# OCB.net
KiCad netlist of a schematic drawn in Altium Designer
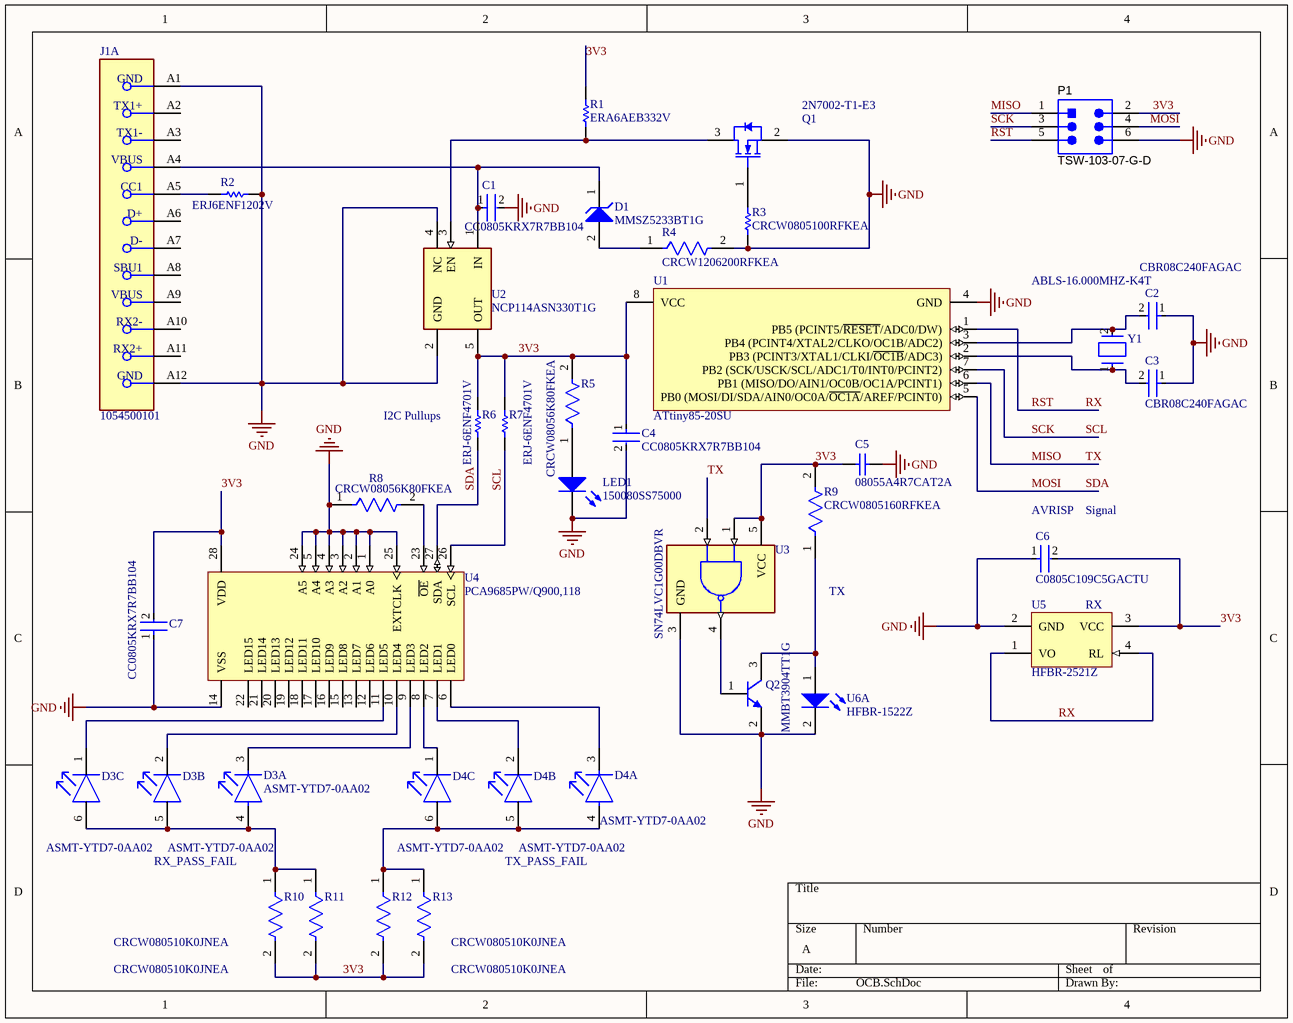
[diagram p0: OCB.SchDoc]

(export (version "E")
  (design (tool "Eeschema 10.0.6"))
  (components
    (comp (ref "C1")
      (value "CC0805KRX7R7BB104")
      (footprint "FP-CC0805-0_85-MFG")
      (description "CAP CER 0.1UF 16V X7R 0805")
      (fields
        (field (name "MANUFACTURER") "Yageo")
        (field (name "OCTOPART") "https://octopart.com/cc0805krx7r7bb104-yageo-39467769")
      )
      (libsource (lib "Altium Content Vault") (part "11868f565c42a9108669ba33697ecf6"))
    )
    (comp (ref "C2")
      (value "CBR08C240FAGAC")
      (footprint "FP-CBR08C-MFG")
      (description "CBR0805 24 pF C0G 30ppm/°C 1.00% 250 V")
      (fields (field (name "TOLERANCE") "0.01"))
      (libsource (lib "Altium Content Vault") (part "11868f565c42a9108669ba33697ecf6"))
    )
    (comp (ref "C3")
      (value "CBR08C240FAGAC")
      (footprint "FP-CBR08C-MFG")
      (description "CBR0805 24 pF C0G 30ppm/°C 1.00% 250 V")
      (fields (field (name "TOLERANCE") "0.01"))
      (libsource (lib "Altium Content Vault") (part "11868f565c42a9108669ba33697ecf6"))
    )
    (comp (ref "C4")
      (value "CC0805KRX7R7BB104")
      (footprint "FP-CC0805-0_85-MFG")
      (description "CAP CER 0.1UF 16V X7R 0805")
      (fields
        (field (name "MANUFACTURER") "Yageo")
        (field (name "OCTOPART") "https://octopart.com/cc0805krx7r7bb104-yageo-39467769")
      )
      (libsource (lib "Altium Content Vault") (part "11868f565c42a9108669ba33697ecf6"))
    )
    (comp (ref "C5")
      (value "08055A4R7CAT2A")
      (footprint "CAPC2013X71X50ML20T25")
      (fields (field (name "MANUFACTURER") "AVX Interconnect / Elco"))
      (libsource (lib "Altium Content Vault") (part "CAP"))
    )
    (comp (ref "C6")
      (value "C0805C109C5GACTU")
      (footprint "FP-C0805C-DN-MFG")
      (description "CAP CER 1PF 50V C0G/NP0 0805")
      (fields (field (name "MANUFACTURER") "KEMET") (field (name "TOLERANCE") "0.25 pF"))
      (libsource (lib "Altium Content Vault") (part "b4654b650e69147ec39a6b967a45e02"))
    )
    (comp (ref "C7")
      (value "CC0805KRX7R7BB104")
      (footprint "FP-CC0805-0_85-MFG")
      (description "CAP CER 0.1UF 16V X7R 0805")
      (fields
        (field (name "MANUFACTURER") "Yageo")
        (field (name "OCTOPART") "https://octopart.com/cc0805krx7r7bb104-yageo-39467769")
      )
      (libsource (lib "Altium Content Vault") (part "11868f565c42a9108669ba33697ecf6"))
    )
    (comp (ref "D1")
      (value "MMSZ5233BT1G")
      (footprint "ONSC-SOD-123-2-425-04_V")
      (description "Zener Voltage Regulator, 500 mW, 2-Pin SOD-123, Pb-Free, Tape and Reel")
      (fields (field (name "MANUFACTURER") "On Semiconductor"))
      (libsource (lib "Altium Content Vault") (part "ONSC-K1A2-2"))
    )
    (comp (ref "D3")
      (value "ASMT-YTD7-0AA02")
      (footprint "FP-PLCC-6-MFG")
      (description "LED RGB DIFFUSED 6PLCC SMD")
      (fields
        (field (name "MANUFACTURER") "Broadcom")
        (field (name "OCTOPART") "https://octopart.com/asmt-ytd7-0aa02-broadcom-71127359")
      )
      (libsource (lib "Altium Content Vault") (part "a8d7b0c4ab3168287692aa145c184e1"))
    )
    (comp (ref "D4")
      (value "ASMT-YTD7-0AA02")
      (footprint "FP-PLCC-6-MFG")
      (description "LED RGB DIFFUSED 6PLCC SMD")
      (fields
        (field (name "MANUFACTURER") "Broadcom")
        (field (name "OCTOPART") "https://octopart.com/asmt-ytd7-0aa02-broadcom-71127359")
      )
      (libsource (lib "Altium Content Vault") (part "a8d7b0c4ab3168287692aa145c184e1"))
    )
    (comp (ref "J1")
      (value "1054500101")
      (footprint "FP-1054500101-MFG")
      (description "CONN RCP USB3.1 TYPEC 24P SMD RA")
      (fields
        (field (name "MANUFACTURER") "Molex")
        (field (name "OCTOPART") "https://octopart.com/105450-0101-molex-68082325")
      )
      (libsource (lib "Altium Content Vault") (part "9808b19ecaf079fb99eed69f0495cd0"))
    )
    (comp (ref "LED1")
      (value "150080SS75000")
      (footprint "0805_A")
      (description "SMD mono-color Chip LED, WL-SMCW, Super Red")
      (fields (field (name "MANUFACTURER") "Wuerth Elektronik"))
      (libsource (lib "Altium Content Vault") (part "WE-LED_K1A2-2"))
    )
    (comp (ref "P1")
      (value "TSW-103-07-G-D")
      (footprint "SMTC-TSW-103-07-G-D_V")
      (fields (field (name "MANUFACTURER") "Samtec-Inc."))
      (libsource (lib "Altium Content Vault") (part "CN-2P-M-R6"))
    )
    (comp (ref "Q1")
      (value "2N7002-T1-E3")
      (footprint "VISH-TO-236-3_A_L")
      (description "N-Channel MOSFET, 115 mA, 60 V, -55 to 150 degC, 3-Pin SOT23, RoHS, Tape and Reel")
      (fields (field (name "MANUFACTURER") "Vishay"))
      (libsource (lib "Altium Content Vault") (part "NEMOS-GSD-3"))
    )
    (comp (ref "Q2")
      (value "MMBT3904TT1G")
      (footprint "ONSC-SC-75-3-463-01_V")
      (description "General Purpose Transistor, NPN Silicon, 3-Pin SC-75, Pb-Free, Tape and Reel")
      (fields (field (name "MANUFACTURER") "On Semiconductor"))
      (libsource (lib "Altium Content Vault") (part "ONSC-NPN-B1E2C3-3"))
    )
    (comp (ref "R1")
      (value "ERA6AEB332V")
      (footprint "RESC2013X60X40NL20T25")
      (fields (field (name "MANUFACTURER") "Panasonic"))
      (libsource (lib "Altium Content Vault") (part "RES"))
    )
    (comp (ref "R2")
      (value "ERJ6ENF1202V")
      (footprint "RESC2013X70X40ML20T20")
      (fields (field (name "MANUFACTURER") "Panasonic"))
      (libsource (lib "Altium Content Vault") (part "RES"))
    )
    (comp (ref "R3")
      (value "CRCW0805100RFKEA")
      (footprint "RESC2013X50X30LL20T20")
      (fields (field (name "MANUFACTURER") "Vishay Dale"))
      (libsource (lib "Altium Content Vault") (part "RES"))
    )
    (comp (ref "R4")
      (value "CRCW1206200RFKEA")
      (footprint "FP-CRCW1206-e3-IPC_C")
      (description "RES Thick Film, 200Ω, 1%, 0.25W, 100ppm/°C, 1206")
      (fields (field (name "TOLERANCE") "1%"))
      (libsource (lib "Altium Content Vault") (part "1029c3af85768c4190bb7ad29bc67b5"))
    )
    (comp (ref "R5")
      (value "CRCW08056K80FKEA")
      (footprint "FP-CRCW0805-e3-IPC_A")
      (description "RES Thick Film, 6.8kΩ, 1%, 0.125W, 100ppm/°C, 0805")
      (fields (field (name "TOLERANCE") "1%"))
      (libsource (lib "Altium Content Vault") (part "1029c3af85768c4190bb7ad29bc67b5"))
    )
    (comp (ref "R6")
      (value "ERJ-6ENF4701V")
      (footprint "RESC2013X70X40NL20T20")
      (description "Chip Resistor, 4.7 KOhm, +/- 1%, 0.125 W, -55 to 155 degC, 0805 (2012 Metric), RoHS, Tape and Reel")
      (fields (field (name "MANUFACTURER") "Panasonic"))
      (libsource (lib "Altium Content Vault") (part "RES-2"))
    )
    (comp (ref "R7")
      (value "ERJ-6ENF4701V")
      (footprint "RESC2013X70X40NL20T20")
      (description "Chip Resistor, 4.7 KOhm, +/- 1%, 0.125 W, -55 to 155 degC, 0805 (2012 Metric), RoHS, Tape and Reel")
      (fields (field (name "MANUFACTURER") "Panasonic"))
      (libsource (lib "Altium Content Vault") (part "RES-2"))
    )
    (comp (ref "R8")
      (value "CRCW08056K80FKEA")
      (footprint "FP-CRCW0805-e3-IPC_A")
      (description "RES Thick Film, 6.8kΩ, 1%, 0.125W, 100ppm/°C, 0805")
      (fields (field (name "TOLERANCE") "1%"))
      (libsource (lib "Altium Content Vault") (part "1029c3af85768c4190bb7ad29bc67b5"))
    )
    (comp (ref "R9")
      (value "CRCW0805160RFKEA")
      (footprint "FP-CRCW0805-e3-IPC_C")
      (description "RES Thick Film, 160Ω, 1%, 0.125W, 100ppm/°C, 0805")
      (fields (field (name "TOLERANCE") "1%"))
      (libsource (lib "Altium Content Vault") (part "1029c3af85768c4190bb7ad29bc67b5"))
    )
    (comp (ref "R10")
      (value "CRCW080510K0JNEA")
      (footprint "FP-CRCW0805-e3-IPC_C")
      (description "RES Thick Film, 10kΩ, 5%, 0.125W, 200ppm/°C, 0805")
      (fields (field (name "TOLERANCE") "5%"))
      (libsource (lib "Altium Content Vault") (part "1029c3af85768c4190bb7ad29bc67b5"))
    )
    (comp (ref "R11")
      (value "CRCW080510K0JNEA")
      (footprint "FP-CRCW0805-e3-IPC_C")
      (description "RES Thick Film, 10kΩ, 5%, 0.125W, 200ppm/°C, 0805")
      (fields (field (name "TOLERANCE") "5%"))
      (libsource (lib "Altium Content Vault") (part "1029c3af85768c4190bb7ad29bc67b5"))
    )
    (comp (ref "R12")
      (value "CRCW080510K0JNEA")
      (footprint "FP-CRCW0805-e3-IPC_C")
      (description "RES Thick Film, 10kΩ, 5%, 0.125W, 200ppm/°C, 0805")
      (fields (field (name "TOLERANCE") "5%"))
      (libsource (lib "Altium Content Vault") (part "1029c3af85768c4190bb7ad29bc67b5"))
    )
    (comp (ref "R13")
      (value "CRCW080510K0JNEA")
      (footprint "FP-CRCW0805-e3-IPC_C")
      (description "RES Thick Film, 10kΩ, 5%, 0.125W, 200ppm/°C, 0805")
      (fields (field (name "TOLERANCE") "5%"))
      (libsource (lib "Altium Content Vault") (part "1029c3af85768c4190bb7ad29bc67b5"))
    )
    (comp (ref "U1")
      (value "ATtiny85-20SU")
      (footprint "8S2_M")
      (libsource (lib "Altium Content Vault") (part "MC-8B-ATT25-IL8"))
    )
    (comp (ref "U2")
      (value "NCP114ASN330T1G")
      (footprint "FP-483-MFG")
      (description "IC REG LINEAR 3.3V 300MA 5TSOP")
      (fields
        (field (name "MANUFACTURER") "ON Semiconductor")
        (field (name "OCTOPART") "https://octopart.com/ncp114asn330t1g-on+semiconductor-74628742")
      )
      (libsource (lib "Altium Content Vault") (part "57814aa37072aacea77ef0fe9350350"))
    )
    (comp (ref "U3")
      (value "SN74LVC1G00DBVR")
      (footprint "FP-DBV0005A-MFG")
      (description "IC GATE NAND 1CH 2-INP SOT23-5")
      (fields
        (field (name "MANUFACTURER") "Texas Instruments")
        (field (name "OCTOPART") "https://octopart.com/sn74lvc1g00dbvr-texas+instruments-465560")
      )
      (libsource (lib "Altium Content Vault") (part "d7ecd29f903bbf85ac132faf7c71588"))
    )
    (comp (ref "U4")
      (value "PCA9685PW/Q900,118")
      (footprint "SOT361-1_V")
      (fields (field (name "PARTNUMBER") "PCA9685"))
      (libsource (lib "Altium Content Vault") (part "NXP-PCA9685-SOT361-1"))
    )
    (comp (ref "U5")
      (value "HFBR-2521Z")
      (footprint "BCM-HFBR-2521Z-4")
      (description "The Versatile Fiber Optic Connection, 5 MBd, -40 to 85 degC, 4-Pin, RoHS, Rail/Tube")
      (fields (field (name "MANUFACTURER") "Broadcom"))
      (libsource (lib "Altium Content Vault") (part "BCM-HFBR-2521Z-4"))
    )
    (comp (ref "U6")
      (value "HFBR-1522Z")
      (footprint "AVAG-HFBR-15X2Z_V")
      (description "The Versatile Fiber Optic Connection, 5 V, -40 to 85 degC, 6-Pin THD, RoHS, Tube")
      (fields (field (name "MANUFACTURER") "Avago"))
      (libsource (lib "Altium Content Vault") (part "AVAG-HFBR-15X2Z-6"))
    )
    (comp (ref "Y1")
      (value "ABLS-16.000MHZ-K4T")
      (footprint "FP-ABLS-MFG")
      (description "CRYSTAL 16.0000MHZ 18PF SMD")
      (fields
        (field (name "TOLERANCE") "30ppm")
        (field (name "OCTOPART") "https://octopart.com/abls-16.000mhz-k4t-abracon-18618626")
      )
      (libsource (lib "Altium Content Vault") (part "c23a69dc6c9e2f18f2079038eb95dd1"))
    )
  )
  (nets
    (net (code "1") (name "/3V3") (class "Default")
      (node (ref "C4") (pin "1") (pinfunction "1_1") (pintype "passive"))
      (node (ref "C5") (pin "2") (pinfunction "2_2") (pintype "passive"))
      (node (ref "C6") (pin "2") (pinfunction "2_2") (pintype "passive"))
      (node (ref "C7") (pin "2") (pinfunction "2_2") (pintype "passive"))
      (node (ref "P1") (pin "2") (pinfunction "2_2") (pintype "passive"))
      (node (ref "R1") (pin "2") (pinfunction "2_2") (pintype "passive"))
      (node (ref "R10") (pin "2") (pinfunction "2_2") (pintype "passive"))
      (node (ref "R11") (pin "2") (pinfunction "2_2") (pintype "passive"))
      (node (ref "R12") (pin "2") (pinfunction "2_2") (pintype "passive"))
      (node (ref "R13") (pin "2") (pinfunction "2_2") (pintype "passive"))
      (node (ref "R5") (pin "2") (pinfunction "2_2") (pintype "passive"))
      (node (ref "R6") (pin "2") (pinfunction "2_2") (pintype "passive"))
      (node (ref "R7") (pin "2") (pinfunction "2_2") (pintype "passive"))
      (node (ref "R9") (pin "2") (pinfunction "2_2") (pintype "passive"))
      (node (ref "U1") (pin "8") (pinfunction "VCC_8") (pintype "power_in"))
      (node (ref "U2") (pin "5") (pinfunction "OUT_5") (pintype "power_in"))
      (node (ref "U3") (pin "1") (pinfunction "A_1") (pintype "input"))
      (node (ref "U3") (pin "5") (pinfunction "VCC_5") (pintype "power_in"))
      (node (ref "U4") (pin "28") (pinfunction "VDD_28") (pintype "power_in"))
      (node (ref "U5") (pin "3") (pinfunction "VCC_3") (pintype "power_in"))
    )
    (net (code "2") (name "/MISO") (class "Default")
      (node (ref "P1") (pin "1") (pinfunction "1_1") (pintype "passive"))
      (node (ref "U1") (pin "6") (pinfunction "PB1_(MISO/DO/AIN1/OC0B/OC1A/PCINT1)_6") (pintype "bidirectional"))
      (node (ref "U3") (pin "2") (pinfunction "B_2") (pintype "input"))
    )
    (net (code "3") (name "/MOSI") (class "Default")
      (node (ref "P1") (pin "4") (pinfunction "4_4") (pintype "passive"))
      (node (ref "R6") (pin "1") (pinfunction "1_1") (pintype "passive"))
      (node (ref "U1") (pin "5") (pinfunction "PB0_(MOSI/DI/SDA/AIN0/OC0A/~{OC1A}/AREF/PCINT0)_5") (pintype "bidirectional"))
      (node (ref "U4") (pin "27") (pinfunction "SDA_27") (pintype "bidirectional"))
    )
    (net (code "4") (name "/RST") (class "Default")
      (node (ref "P1") (pin "5") (pinfunction "5_5") (pintype "passive"))
      (node (ref "U1") (pin "1") (pinfunction "PB5_(PCINT5/~{RESET}/ADC0/DW)_1") (pintype "bidirectional"))
      (node (ref "U5") (pin "1") (pinfunction "VO_1") (pintype "power_in"))
      (node (ref "U5") (pin "4") (pinfunction "RL_4") (pintype "input"))
    )
    (net (code "5") (name "/SCK") (class "Default")
      (node (ref "P1") (pin "3") (pinfunction "3_3") (pintype "passive"))
      (node (ref "R7") (pin "1") (pinfunction "1_1") (pintype "passive"))
      (node (ref "U1") (pin "7") (pinfunction "PB2_(SCK/USCK/SCL/ADC1/T0/INT0/PCINT2)_7") (pintype "bidirectional"))
      (node (ref "U4") (pin "26") (pinfunction "SCL_26") (pintype "input"))
    )
    (net (code "6") (name "GND") (class "Default")
      (node (ref "C1") (pin "2") (pinfunction "2_2") (pintype "passive"))
      (node (ref "C2") (pin "1") (pinfunction "1_1") (pintype "passive"))
      (node (ref "C3") (pin "1") (pinfunction "1_1") (pintype "passive"))
      (node (ref "C4") (pin "2") (pinfunction "2_2") (pintype "passive"))
      (node (ref "C5") (pin "1") (pinfunction "1_1") (pintype "passive"))
      (node (ref "C6") (pin "1") (pinfunction "1_1") (pintype "passive"))
      (node (ref "C7") (pin "1") (pinfunction "1_1") (pintype "passive"))
      (node (ref "J1") (pin "A1") (pinfunction "GND_A1") (pintype "passive"))
      (node (ref "J1") (pin "A12") (pinfunction "GND_A12") (pintype "passive"))
      (node (ref "LED1") (pin "1") (pinfunction "K_1") (pintype "passive"))
      (node (ref "P1") (pin "6") (pinfunction "6_6") (pintype "passive"))
      (node (ref "Q1") (pin "2") (pinfunction "S_2") (pintype "passive"))
      (node (ref "Q2") (pin "2") (pinfunction "E_2") (pintype "passive"))
      (node (ref "R2") (pin "2") (pinfunction "2_2") (pintype "passive"))
      (node (ref "R3") (pin "1") (pinfunction "1_1") (pintype "passive"))
      (node (ref "R4") (pin "2") (pinfunction "2_2") (pintype "passive"))
      (node (ref "R8") (pin "1") (pinfunction "1_1") (pintype "passive"))
      (node (ref "U1") (pin "4") (pinfunction "GND_4") (pintype "power_in"))
      (node (ref "U2") (pin "2") (pinfunction "GND_2") (pintype "power_in"))
      (node (ref "U2") (pin "4") (pinfunction "NC_4") (pintype "passive"))
      (node (ref "U3") (pin "3") (pinfunction "GND_3") (pintype "power_in"))
      (node (ref "U4") (pin "1") (pinfunction "A0_1") (pintype "input"))
      (node (ref "U4") (pin "14") (pinfunction "VSS_14") (pintype "power_in"))
      (node (ref "U4") (pin "2") (pinfunction "A1_2") (pintype "input"))
      (node (ref "U4") (pin "24") (pinfunction "A5_24") (pintype "input"))
      (node (ref "U4") (pin "25") (pinfunction "EXTCLK_25") (pintype "input"))
      (node (ref "U4") (pin "3") (pinfunction "A2_3") (pintype "input"))
      (node (ref "U4") (pin "4") (pinfunction "A3_4") (pintype "input"))
      (node (ref "U4") (pin "5") (pinfunction "A4_5") (pintype "input"))
      (node (ref "U5") (pin "2") (pinfunction "GND_2") (pintype "power_in"))
      (node (ref "U6") (pin "2") (pinfunction "CATHODE_2") (pintype "passive"))
    )
    (net (code "7") (name "Net-(D1-A)") (class "Default")
      (node (ref "D1") (pin "2") (pinfunction "A_2") (pintype "passive"))
      (node (ref "R4") (pin "1") (pinfunction "1_1") (pintype "passive"))
    )
    (net (code "8") (name "Net-(D1-K)") (class "Default")
      (node (ref "C1") (pin "1") (pinfunction "1_1") (pintype "passive"))
      (node (ref "D1") (pin "1") (pinfunction "K_1") (pintype "passive"))
      (node (ref "J1") (pin "A4") (pinfunction "VBUS_A4") (pintype "passive"))
      (node (ref "U2") (pin "1") (pinfunction "IN_1") (pintype "power_in"))
    )
    (net (code "9") (name "Net-(D3A-Anode(Red))") (class "Default")
      (node (ref "D3") (pin "4") (pinfunction "Anode(Red)_4") (pintype "passive"))
      (node (ref "D3") (pin "5") (pinfunction "Anode(Green)_5") (pintype "passive"))
      (node (ref "D3") (pin "6") (pinfunction "Anode(Blue)_6") (pintype "passive"))
      (node (ref "R10") (pin "1") (pinfunction "1_1") (pintype "passive"))
      (node (ref "R11") (pin "1") (pinfunction "1_1") (pintype "passive"))
    )
    (net (code "10") (name "Net-(D3A-Cathode(Red))") (class "Default")
      (node (ref "D3") (pin "3") (pinfunction "Cathode(Red)_3") (pintype "passive"))
      (node (ref "U4") (pin "9") (pinfunction "LED3_9") (pintype "tri_state"))
    )
    (net (code "11") (name "Net-(D3B-Cathode(Green))") (class "Default")
      (node (ref "D3") (pin "2") (pinfunction "Cathode(Green)_2") (pintype "passive"))
      (node (ref "U4") (pin "10") (pinfunction "LED4_10") (pintype "tri_state"))
    )
    (net (code "12") (name "Net-(D3C-Cathode(Blue))") (class "Default")
      (node (ref "D3") (pin "1") (pinfunction "Cathode(Blue)_1") (pintype "passive"))
      (node (ref "U4") (pin "11") (pinfunction "LED5_11") (pintype "tri_state"))
    )
    (net (code "13") (name "Net-(D4A-Anode(Red))") (class "Default")
      (node (ref "D4") (pin "4") (pinfunction "Anode(Red)_4") (pintype "passive"))
      (node (ref "D4") (pin "5") (pinfunction "Anode(Green)_5") (pintype "passive"))
      (node (ref "D4") (pin "6") (pinfunction "Anode(Blue)_6") (pintype "passive"))
      (node (ref "R12") (pin "1") (pinfunction "1_1") (pintype "passive"))
      (node (ref "R13") (pin "1") (pinfunction "1_1") (pintype "passive"))
    )
    (net (code "14") (name "Net-(D4A-Cathode(Red))") (class "Default")
      (node (ref "D4") (pin "3") (pinfunction "Cathode(Red)_3") (pintype "passive"))
      (node (ref "U4") (pin "6") (pinfunction "LED0_6") (pintype "tri_state"))
    )
    (net (code "15") (name "Net-(D4B-Cathode(Green))") (class "Default")
      (node (ref "D4") (pin "2") (pinfunction "Cathode(Green)_2") (pintype "passive"))
      (node (ref "U4") (pin "7") (pinfunction "LED1_7") (pintype "tri_state"))
    )
    (net (code "16") (name "Net-(D4C-Cathode(Blue))") (class "Default")
      (node (ref "D4") (pin "1") (pinfunction "Cathode(Blue)_1") (pintype "passive"))
      (node (ref "U4") (pin "8") (pinfunction "LED2_8") (pintype "tri_state"))
    )
    (net (code "17") (name "Net-(J1A-CC1)") (class "Default")
      (node (ref "J1") (pin "A5") (pinfunction "CC1_A5") (pintype "passive"))
      (node (ref "R2") (pin "1") (pinfunction "1_1") (pintype "passive"))
    )
    (net (code "18") (name "Net-(LED1-A)") (class "Default")
      (node (ref "LED1") (pin "2") (pinfunction "A_2") (pintype "passive"))
      (node (ref "R5") (pin "1") (pinfunction "1_1") (pintype "passive"))
    )
    (net (code "19") (name "Net-(Q1-D)") (class "Default")
      (node (ref "Q1") (pin "3") (pinfunction "D_3") (pintype "passive"))
      (node (ref "R1") (pin "1") (pinfunction "1_1") (pintype "passive"))
      (node (ref "U2") (pin "3") (pinfunction "EN_3") (pintype "input"))
    )
    (net (code "20") (name "Net-(Q1-G)") (class "Default")
      (node (ref "Q1") (pin "1") (pinfunction "G_1") (pintype "passive"))
      (node (ref "R3") (pin "2") (pinfunction "2_2") (pintype "passive"))
    )
    (net (code "21") (name "Net-(Q2-B)") (class "Default")
      (node (ref "Q2") (pin "1") (pinfunction "B_1") (pintype "passive"))
      (node (ref "U3") (pin "4") (pinfunction "Y_4") (pintype "output"))
    )
    (net (code "22") (name "Net-(Q2-C)") (class "Default")
      (node (ref "Q2") (pin "3") (pinfunction "C_3") (pintype "passive"))
      (node (ref "R9") (pin "1") (pinfunction "1_1") (pintype "passive"))
      (node (ref "U6") (pin "1") (pinfunction "ANODE_1") (pintype "passive"))
    )
    (net (code "23") (name "Net-(U1-PB3_(PCINT3{slash}XTAL1{slash}CLKI{slash}~{OC1B}{slash}ADC3))") (class "Default")
      (node (ref "C3") (pin "2") (pinfunction "2_2") (pintype "passive"))
      (node (ref "U1") (pin "2") (pinfunction "PB3_(PCINT3/XTAL1/CLKI/~{OC1B}/ADC3)_2") (pintype "bidirectional"))
      (node (ref "Y1") (pin "1") (pinfunction "1_1") (pintype "passive"))
    )
    (net (code "24") (name "Net-(U1-PB4_(PCINT4{slash}XTAL2{slash}CLKO{slash}OC1B{slash}ADC2))") (class "Default")
      (node (ref "C2") (pin "2") (pinfunction "2_2") (pintype "passive"))
      (node (ref "U1") (pin "3") (pinfunction "PB4_(PCINT4/XTAL2/CLKO/OC1B/ADC2)_3") (pintype "bidirectional"))
      (node (ref "Y1") (pin "2") (pinfunction "2_2") (pintype "passive"))
    )
    (net (code "25") (name "Net-(U4-~{OE})") (class "Default")
      (node (ref "R8") (pin "2") (pinfunction "2_2") (pintype "passive"))
      (node (ref "U4") (pin "23") (pinfunction "~{OE}_23") (pintype "input"))
    )
    (net (code "26") (name "unconnected-(J1A-D+-PadA6)") (class "Default")
      (node (ref "J1") (pin "A6") (pinfunction "D+_A6") (pintype "passive"))
    )
    (net (code "27") (name "unconnected-(J1A-D--PadA7)") (class "Default")
      (node (ref "J1") (pin "A7") (pinfunction "D-_A7") (pintype "passive"))
    )
    (net (code "28") (name "unconnected-(J1A-RX2+-PadA11)") (class "Default")
      (node (ref "J1") (pin "A11") (pinfunction "RX2+_A11") (pintype "passive"))
    )
    (net (code "29") (name "unconnected-(J1A-RX2--PadA10)") (class "Default")
      (node (ref "J1") (pin "A10") (pinfunction "RX2-_A10") (pintype "passive"))
    )
    (net (code "30") (name "unconnected-(J1A-SBU1-PadA8)") (class "Default")
      (node (ref "J1") (pin "A8") (pinfunction "SBU1_A8") (pintype "passive"))
    )
    (net (code "31") (name "unconnected-(J1A-TX1+-PadA2)") (class "Default")
      (node (ref "J1") (pin "A2") (pinfunction "TX1+_A2") (pintype "passive"))
    )
    (net (code "32") (name "unconnected-(J1A-TX1--PadA3)") (class "Default")
      (node (ref "J1") (pin "A3") (pinfunction "TX1-_A3") (pintype "passive"))
    )
    (net (code "33") (name "unconnected-(J1A-VBUS-PadA9)") (class "Default")
      (node (ref "J1") (pin "A9") (pinfunction "VBUS_A9") (pintype "passive"))
    )
    (net (code "34") (name "unconnected-(U4-LED6-Pad12)") (class "Default")
      (node (ref "U4") (pin "12") (pinfunction "LED6_12") (pintype "tri_state"))
    )
    (net (code "35") (name "unconnected-(U4-LED7-Pad13)") (class "Default")
      (node (ref "U4") (pin "13") (pinfunction "LED7_13") (pintype "tri_state"))
    )
    (net (code "36") (name "unconnected-(U4-LED8-Pad15)") (class "Default")
      (node (ref "U4") (pin "15") (pinfunction "LED8_15") (pintype "tri_state"))
    )
    (net (code "37") (name "unconnected-(U4-LED9-Pad16)") (class "Default")
      (node (ref "U4") (pin "16") (pinfunction "LED9_16") (pintype "tri_state"))
    )
    (net (code "38") (name "unconnected-(U4-LED10-Pad17)") (class "Default")
      (node (ref "U4") (pin "17") (pinfunction "LED10_17") (pintype "tri_state"))
    )
    (net (code "39") (name "unconnected-(U4-LED11-Pad18)") (class "Default")
      (node (ref "U4") (pin "18") (pinfunction "LED11_18") (pintype "tri_state"))
    )
    (net (code "40") (name "unconnected-(U4-LED12-Pad19)") (class "Default")
      (node (ref "U4") (pin "19") (pinfunction "LED12_19") (pintype "tri_state"))
    )
    (net (code "41") (name "unconnected-(U4-LED13-Pad20)") (class "Default")
      (node (ref "U4") (pin "20") (pinfunction "LED13_20") (pintype "tri_state"))
    )
    (net (code "42") (name "unconnected-(U4-LED14-Pad21)") (class "Default")
      (node (ref "U4") (pin "21") (pinfunction "LED14_21") (pintype "tri_state"))
    )
    (net (code "43") (name "unconnected-(U4-LED15-Pad22)") (class "Default")
      (node (ref "U4") (pin "22") (pinfunction "LED15_22") (pintype "tri_state"))
    )
  )
)
